# airwisk_bez_transisotru.net
KiCad netlist of a schematic drawn in EAGLE
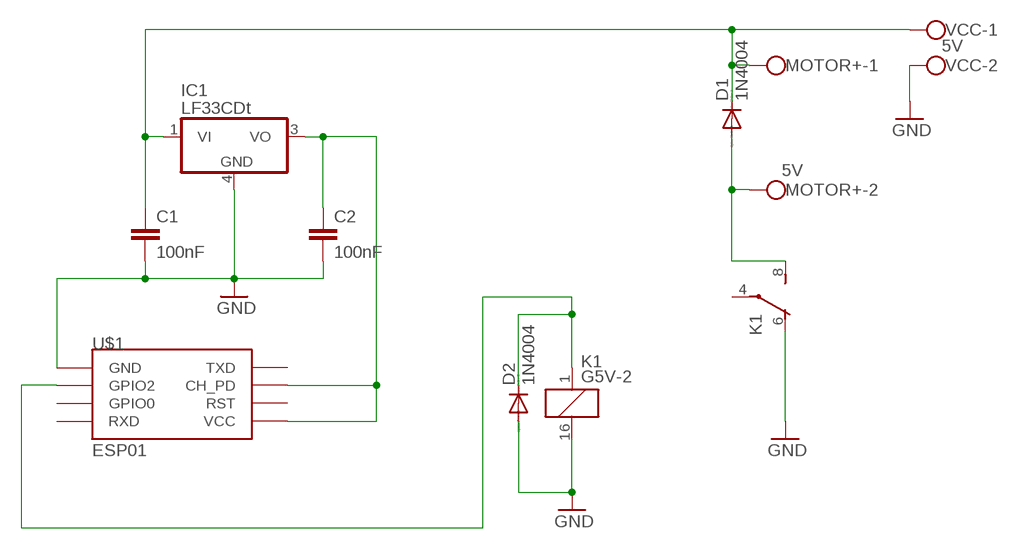
[diagram p0: schematic, sheet 1]

(export (version "E")
  (design (tool "Eeschema 10.0.6"))
  (components
    (comp (ref "C1")
      (value "100nF")
      (footprint "eagle-import:C025-025X050")
      (libsource (lib "eagle-import") (part "C-EU025-025X050"))
    )
    (comp (ref "C2")
      (value "100nF")
      (footprint "eagle-import:C025-025X050")
      (libsource (lib "eagle-import") (part "C-EU025-025X050"))
    )
    (comp (ref "D1")
      (value "1N4004")
      (footprint "eagle-import:DO41-10")
      (libsource (lib "eagle-import") (part "1N4004"))
    )
    (comp (ref "D2")
      (value "1N4004")
      (footprint "eagle-import:DO41-10")
      (libsource (lib "eagle-import") (part "1N4004"))
    )
    (comp (ref "IC1")
      (value "LF33CDt")
      (footprint "eagle-import:DPACK_3")
      (libsource (lib "eagle-import") (part "MC78M05ABDT"))
    )
    (comp (ref "K1")
      (value "G5V-2")
      (footprint "eagle-import:G5V-2")
      (fields (field (name "MPN") "G5V-2 5DC"))
      (libsource (lib "eagle-import") (part "G5V-2"))
    )
    (comp (ref "MOTOR+")
      (value "5V")
      (footprint "eagle-import:W237-102")
      (fields (field (name "MPN") "237-102"))
      (libsource (lib "eagle-import") (part "W237-102"))
    )
    (comp (ref "U$1")
      (value "ESP01")
      (footprint "eagle-import:ESP01")
      (libsource (lib "eagle-import") (part "ESP01"))
    )
    (comp (ref "VCC")
      (value "5V")
      (footprint "eagle-import:W237-102")
      (fields (field (name "MPN") "237-102"))
      (libsource (lib "eagle-import") (part "W237-102"))
    )
  )
  (nets
    (net (code "1") (name "GND") (class "Default")
      (node (ref "C1") (pin "2") (pinfunction "2_2") (pintype "passive"))
      (node (ref "C2") (pin "2") (pinfunction "2_2") (pintype "passive"))
      (node (ref "D2") (pin "A") (pinfunction "A_A") (pintype "passive"))
      (node (ref "IC1") (pin "4") (pinfunction "GND_4") (pintype "passive"))
      (node (ref "K1") (pin "16") (pinfunction "2_16") (pintype "passive"))
      (node (ref "K1") (pin "6") (pinfunction "O_6") (pintype "passive"))
      (node (ref "U$1") (pin "GND") (pinfunction "GND_GND") (pintype "bidirectional"))
      (node (ref "VCC") (pin "2") (pinfunction "KL_2") (pintype "passive"))
    )
    (net (code "2") (name "Net-(D2-PadC)") (class "Default")
      (node (ref "D2") (pin "C") (pinfunction "C_C") (pintype "passive"))
      (node (ref "K1") (pin "1") (pinfunction "1_1") (pintype "passive"))
      (node (ref "U$1") (pin "GPIO2") (pinfunction "GPIO2_GPIO2") (pintype "bidirectional"))
    )
    (net (code "3") (name "Net-(IC1-VI)") (class "Default")
      (node (ref "C1") (pin "1") (pinfunction "1_1") (pintype "passive"))
      (node (ref "D1") (pin "C") (pinfunction "C_C") (pintype "passive"))
      (node (ref "IC1") (pin "1") (pinfunction "VI_1") (pintype "input"))
      (node (ref "MOTOR+") (pin "1") (pinfunction "KL_1") (pintype "passive"))
      (node (ref "VCC") (pin "1") (pinfunction "KL_1") (pintype "passive"))
    )
    (net (code "4") (name "Net-(IC1-VO)") (class "Default")
      (node (ref "C2") (pin "1") (pinfunction "1_1") (pintype "passive"))
      (node (ref "IC1") (pin "3") (pinfunction "VO_3") (pintype "passive"))
      (node (ref "U$1") (pin "CH_PD") (pinfunction "CH_PD_CH_PD") (pintype "bidirectional"))
      (node (ref "U$1") (pin "VCC") (pinfunction "VCC_VCC") (pintype "bidirectional"))
    )
    (net (code "5") (name "Net-(K1A-S)") (class "Default")
      (node (ref "D1") (pin "A") (pinfunction "A_A") (pintype "passive"))
      (node (ref "K1") (pin "8") (pinfunction "S_8") (pintype "passive"))
      (node (ref "MOTOR+") (pin "2") (pinfunction "KL_2") (pintype "passive"))
    )
    (net (code "6") (name "unconnected-(K1A-P-Pad4)") (class "Default")
      (node (ref "K1") (pin "4") (pinfunction "P_4") (pintype "passive"))
    )
    (net (code "7") (name "unconnected-(U$1-PadGPIO0)") (class "Default")
      (node (ref "U$1") (pin "GPIO0") (pinfunction "GPIO0_GPIO0") (pintype "bidirectional"))
    )
    (net (code "8") (name "unconnected-(U$1-PadRST)") (class "Default")
      (node (ref "U$1") (pin "RST") (pinfunction "RST_RST") (pintype "bidirectional"))
    )
    (net (code "9") (name "unconnected-(U$1-RXD-PadRX)") (class "Default")
      (node (ref "U$1") (pin "RX") (pinfunction "RXD_RX") (pintype "bidirectional"))
    )
    (net (code "10") (name "unconnected-(U$1-TXD-PadTX)") (class "Default")
      (node (ref "U$1") (pin "TX") (pinfunction "TXD_TX") (pintype "bidirectional"))
    )
  )
)
